# PWR_LMS3635.net
KiCad netlist of a schematic drawn in Altium Designer
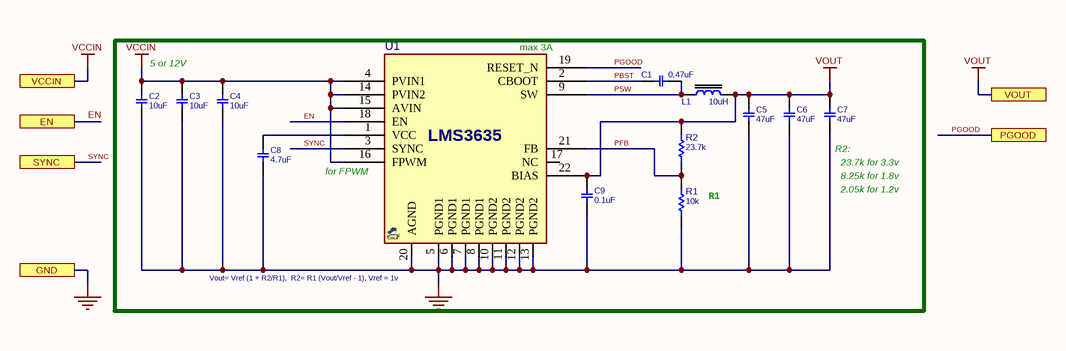
[diagram p0: PWR_LMS3635.SchDoc]

(export (version "E")
  (design (tool "Eeschema 10.0.6"))
  (components
    (comp (ref "C1")
      (value "0.47uF")
      (footprint "C0402A")
      (description "CAP, MLCC")
      (libsource (lib "passive_mlcc_smd") (part "CAP_SMD_MLCC_100n50V"))
    )
    (comp (ref "C2")
      (value "10uF")
      (footprint "C0805")
      (description "CAP, MLCC")
      (fields (field (name "MANF_P#") "CL21A106KAYNNNE") (field (name "MANF") "Samsung"))
      (libsource (lib "passive_smd") (part "CAP_SMD_MLCC"))
    )
    (comp (ref "C3")
      (value "10uF")
      (footprint "C0805")
      (description "CAP, MLCC")
      (fields (field (name "MANF_P#") "CL21A106KAYNNNE") (field (name "MANF") "Samsung"))
      (libsource (lib "passive_smd") (part "CAP_SMD_MLCC"))
    )
    (comp (ref "C4")
      (value "10uF")
      (footprint "C0805")
      (description "CAP, MLCC")
      (fields (field (name "MANF_P#") "CL21A106KAYNNNE") (field (name "MANF") "Samsung"))
      (libsource (lib "passive_smd") (part "CAP_SMD_MLCC"))
    )
    (comp (ref "C5")
      (value "47uF")
      (footprint "C0805A")
      (description "CAP, MLCC")
      (fields (field (name "MANF") "Samsung") (field (name "MANF_P#") "CL21A476MQYNNNE"))
      (libsource (lib "passive_mlcc_smd") (part "CAP_SMD_MLCC_47u25V"))
    )
    (comp (ref "C6")
      (value "47uF")
      (footprint "C0805A")
      (description "CAP, MLCC")
      (fields (field (name "MANF") "Samsung") (field (name "MANF_P#") "CL21A476MQYNNNE"))
      (libsource (lib "passive_mlcc_smd") (part "CAP_SMD_MLCC_47u25V"))
    )
    (comp (ref "C7")
      (value "47uF")
      (footprint "C0805A")
      (description "CAP, MLCC")
      (fields (field (name "MANF") "Samsung") (field (name "MANF_P#") "CL21A476MQYNNNE"))
      (libsource (lib "passive_mlcc_smd") (part "CAP_SMD_MLCC_47u25V"))
    )
    (comp (ref "C8")
      (value "4.7uF")
      (footprint "C0402A")
      (description "CAP, MLCC")
      (fields (field (name "MANF") "Samsung"))
      (libsource (lib "passive_smd") (part "CAP_SMD_MLCC"))
    )
    (comp (ref "C9")
      (value "0.1uF")
      (footprint "C0402A")
      (description "CAP, MLCC, 100nF, 50V, X7R, 10%, 0402C")
      (fields (field (name "MANF") "Murata") (field (name "MANF_P#") "GRM155R61E104"))
      (libsource (lib "passive_mlcc_smd") (part "CAP_SMD_MLCC_100n50V"))
    )
    (comp (ref "L1")
      (value "10uH")
      (footprint "L_7")
      (description "INDUCTOR")
      (fields (field (name "MANF") "KYOCERA AVX") (field (name "MANF_P#") "LMLP07A7M100DTAS"))
      (libsource (lib "chila_passive") (part "IND_SMD_2.2uH_4A"))
    )
    (comp (ref "R1")
      (value "10k")
      (footprint "R0402A")
      (description "RESISTOR, SMD, 20K, 0402")
      (libsource (lib "chila_passive") (part "RES_SMD"))
    )
    (comp (ref "R2")
      (value "23.7k")
      (footprint "R0402A")
      (description "RESISTOR, SMD, 20K, 0402")
      (libsource (lib "chila_passive") (part "RES_SMD"))
    )
    (comp (ref "U1")
      (value "LMS3635")
      (footprint "QFNHR_22_RNL")
      (description "REG, Switching, Buck, 3.9~36Vin, 3.5A, RNL-22")
      (fields (field (name "MANF") "Texas Instruments") (field (name "MANF_P#") "LMS3635MQRNL"))
      (libsource (lib "pwr_switching_buck_lowEMI") (part "VREG_LMS3635MQRNL_QFN22"))
    )
  )
  (nets
    (net (code "1") (name "/EN") (class "Default")
      (node (ref "U1") (pin "18") (pinfunction "EN_18") (pintype "passive"))
    )
    (net (code "2") (name "/PBST") (class "Default")
      (node (ref "C1") (pin "1") (pinfunction "1_1") (pintype "passive"))
      (node (ref "U1") (pin "2") (pinfunction "CBOOT_2") (pintype "passive"))
    )
    (net (code "3") (name "/PFB") (class "Default")
      (node (ref "R1") (pin "1") (pinfunction "1_1") (pintype "passive"))
      (node (ref "R2") (pin "2") (pinfunction "2_2") (pintype "passive"))
      (node (ref "U1") (pin "21") (pinfunction "FB_21") (pintype "passive"))
    )
    (net (code "4") (name "/PGOOD") (class "Default")
      (node (ref "U1") (pin "19") (pinfunction "RESET_N_19") (pintype "passive"))
    )
    (net (code "5") (name "/PSW") (class "Default")
      (node (ref "C1") (pin "2") (pinfunction "2_2") (pintype "passive"))
      (node (ref "L1") (pin "1") (pinfunction "1_1") (pintype "passive"))
      (node (ref "U1") (pin "9") (pinfunction "SW_9") (pintype "passive"))
    )
    (net (code "6") (name "/SYNC") (class "Default")
      (node (ref "U1") (pin "3") (pinfunction "SYNC_3") (pintype "passive"))
    )
    (net (code "7") (name "GND") (class "Default")
      (node (ref "C2") (pin "1") (pinfunction "1_1") (pintype "passive"))
      (node (ref "C3") (pin "1") (pinfunction "1_1") (pintype "passive"))
      (node (ref "C4") (pin "1") (pinfunction "1_1") (pintype "passive"))
      (node (ref "C5") (pin "2") (pinfunction "2_2") (pintype "passive"))
      (node (ref "C6") (pin "2") (pinfunction "2_2") (pintype "passive"))
      (node (ref "C7") (pin "2") (pinfunction "2_2") (pintype "passive"))
      (node (ref "C8") (pin "1") (pinfunction "1_1") (pintype "passive"))
      (node (ref "C9") (pin "2") (pinfunction "2_2") (pintype "passive"))
      (node (ref "R1") (pin "2") (pinfunction "2_2") (pintype "passive"))
      (node (ref "U1") (pin "10") (pinfunction "PGND2_10") (pintype "passive"))
      (node (ref "U1") (pin "11") (pinfunction "PGND2_11") (pintype "passive"))
      (node (ref "U1") (pin "12") (pinfunction "PGND2_12") (pintype "passive"))
      (node (ref "U1") (pin "13") (pinfunction "PGND2_13") (pintype "passive"))
      (node (ref "U1") (pin "20") (pinfunction "AGND_20") (pintype "passive"))
      (node (ref "U1") (pin "5") (pinfunction "PGND1_5") (pintype "passive"))
      (node (ref "U1") (pin "6") (pinfunction "PGND1_6") (pintype "passive"))
      (node (ref "U1") (pin "7") (pinfunction "PGND1_7") (pintype "passive"))
      (node (ref "U1") (pin "8") (pinfunction "PGND1_8") (pintype "passive"))
    )
    (net (code "8") (name "Net-(U1-VCC)") (class "Default")
      (node (ref "C8") (pin "2") (pinfunction "2_2") (pintype "passive"))
      (node (ref "U1") (pin "1") (pinfunction "VCC_1") (pintype "passive"))
    )
    (net (code "9") (name "VCCIN") (class "Default")
      (node (ref "C2") (pin "2") (pinfunction "2_2") (pintype "passive"))
      (node (ref "C3") (pin "2") (pinfunction "2_2") (pintype "passive"))
      (node (ref "C4") (pin "2") (pinfunction "2_2") (pintype "passive"))
      (node (ref "U1") (pin "14") (pinfunction "PVIN2_14") (pintype "passive"))
      (node (ref "U1") (pin "15") (pinfunction "AVIN_15") (pintype "passive"))
      (node (ref "U1") (pin "16") (pinfunction "FPWM_16") (pintype "passive"))
      (node (ref "U1") (pin "4") (pinfunction "PVIN1_4") (pintype "passive"))
    )
    (net (code "10") (name "VOUT") (class "Default")
      (node (ref "C5") (pin "1") (pinfunction "1_1") (pintype "passive"))
      (node (ref "C6") (pin "1") (pinfunction "1_1") (pintype "passive"))
      (node (ref "C7") (pin "1") (pinfunction "1_1") (pintype "passive"))
      (node (ref "C9") (pin "1") (pinfunction "1_1") (pintype "passive"))
      (node (ref "L1") (pin "2") (pinfunction "2_2") (pintype "passive"))
      (node (ref "R2") (pin "1") (pinfunction "1_1") (pintype "passive"))
      (node (ref "U1") (pin "22") (pinfunction "BIAS_22") (pintype "passive"))
    )
    (net (code "11") (name "unconnected-(U1-NC-Pad17)") (class "Default")
      (node (ref "U1") (pin "17") (pinfunction "NC_17") (pintype "passive"))
    )
  )
)
